# Pressure-Sensor-Module.net
KiCad netlist of a schematic drawn in EAGLE
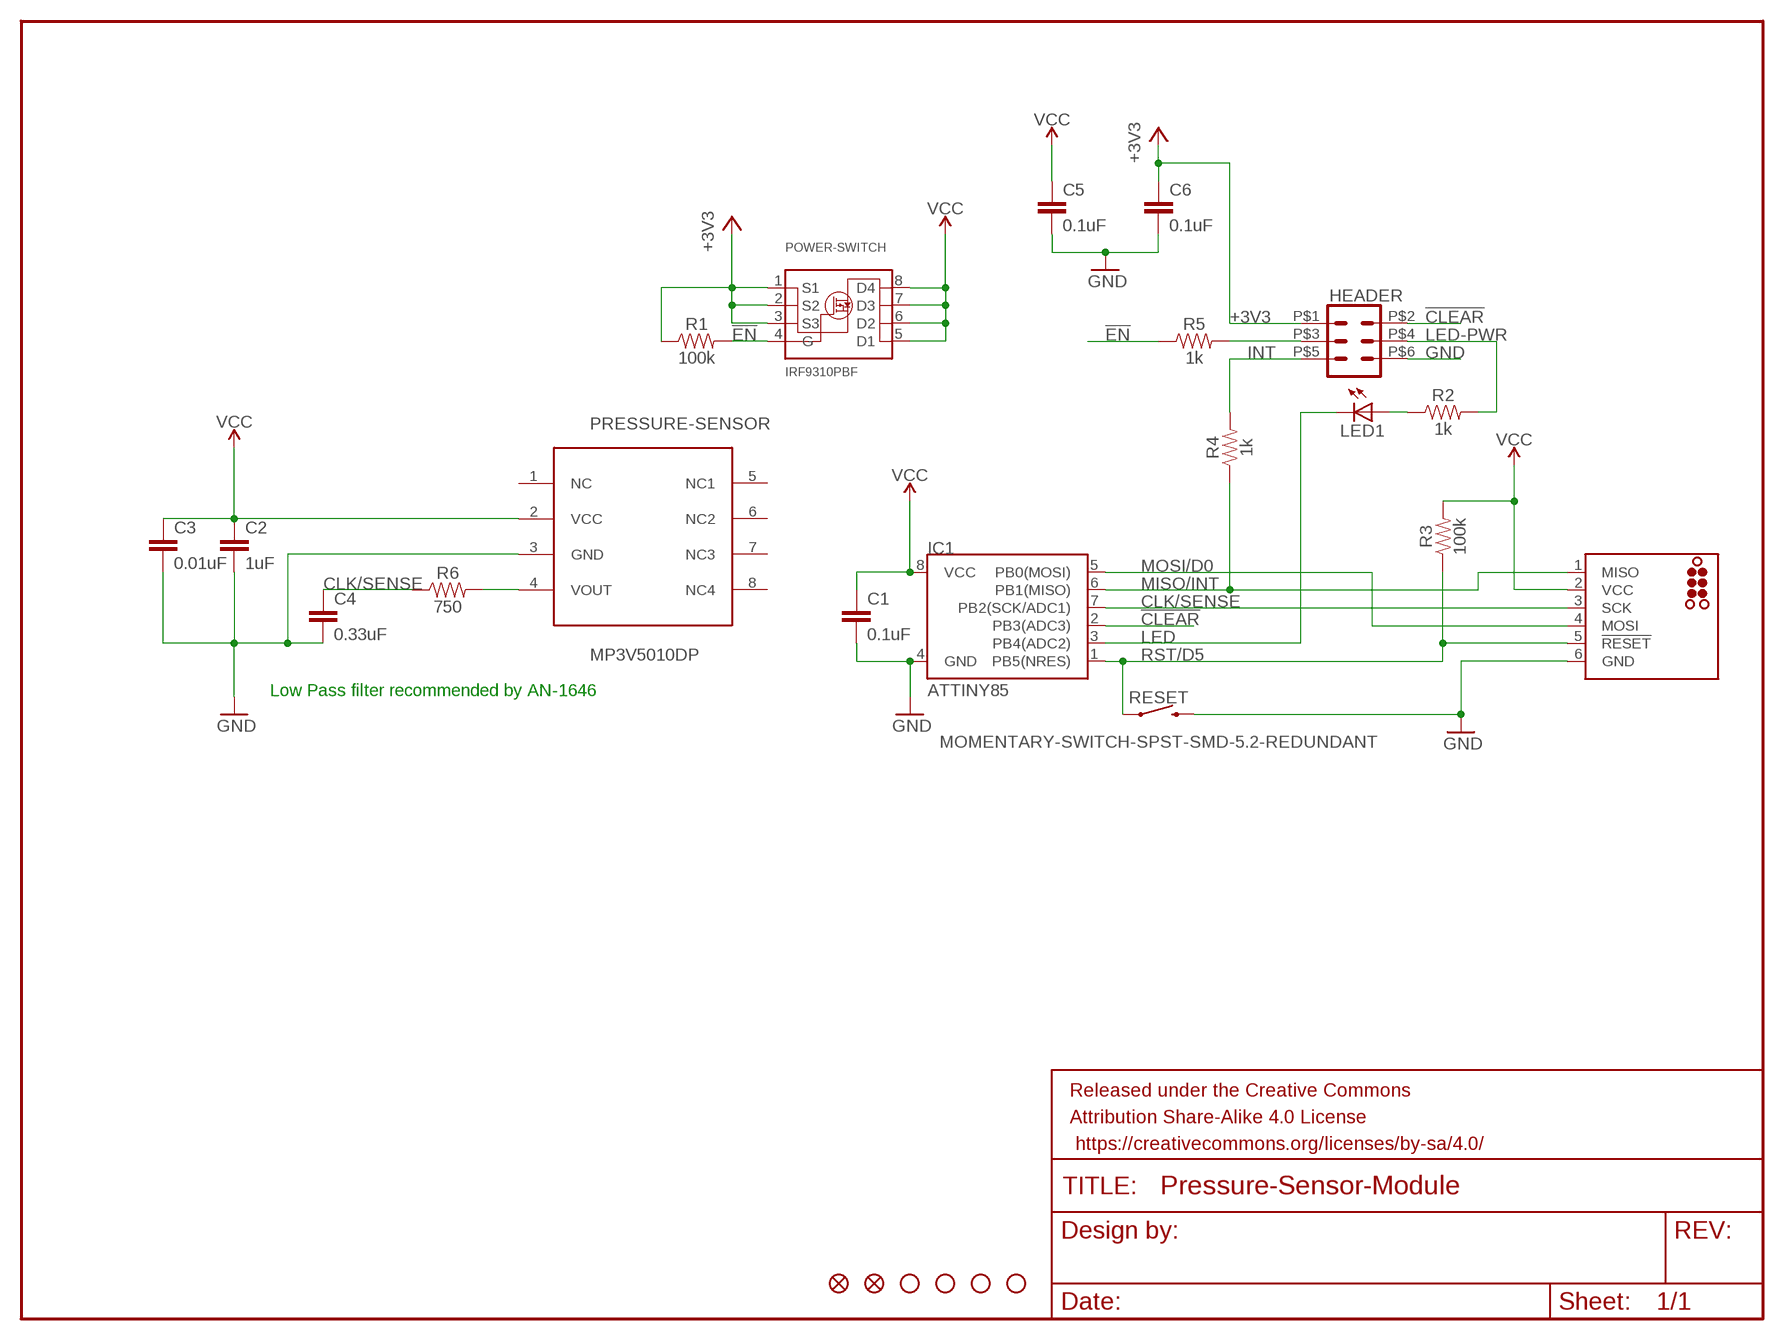
[diagram p0: schematic, sheet 1]

(export (version "E")
  (design (tool "Eeschema 10.0.6"))
  (components
    (comp (ref "C1")
      (value "0.1uF")
      (footprint "eagle-import:0805")
      (libsource (lib "eagle-import") (part "1.0UF-0805-25V-10%"))
    )
    (comp (ref "C2")
      (value "1uF")
      (footprint "eagle-import:0805")
      (libsource (lib "eagle-import") (part "1.0UF-0805-25V-10%"))
    )
    (comp (ref "C3")
      (value "0.01uF")
      (footprint "eagle-import:0805")
      (libsource (lib "eagle-import") (part "1.0UF-0805-25V-10%"))
    )
    (comp (ref "C4")
      (value "0.33uF")
      (footprint "eagle-import:0805")
      (libsource (lib "eagle-import") (part "1.0UF-0805-25V-10%"))
    )
    (comp (ref "C5")
      (value "0.1uF")
      (footprint "eagle-import:0805")
      (libsource (lib "eagle-import") (part "1.0UF-0805-25V-10%"))
    )
    (comp (ref "C6")
      (value "0.1uF")
      (footprint "eagle-import:0805")
      (libsource (lib "eagle-import") (part "1.0UF-0805-25V-10%"))
    )
    (comp (ref "FD1")
      (value "FIDUCIALUFIDUCIAL")
      (footprint "eagle-import:FIDUCIAL-MICRO")
      (libsource (lib "eagle-import") (part "FIDUCIALUFIDUCIAL"))
    )
    (comp (ref "FD2")
      (value "FIDUCIALUFIDUCIAL")
      (footprint "eagle-import:FIDUCIAL-MICRO")
      (libsource (lib "eagle-import") (part "FIDUCIALUFIDUCIAL"))
    )
    (comp (ref "FRAME1")
      (value "FRAME-LETTER")
      (footprint "eagle-import:CREATIVE_COMMONS")
      (libsource (lib "eagle-import") (part "FRAME-LETTER"))
    )
    (comp (ref "HEADER")
      (value "CONN_03X2POGO_PINS")
      (footprint "eagle-import:2X3_POGO")
      (libsource (lib "eagle-import") (part "CONN_03X2POGO_PINS"))
    )
    (comp (ref "IC1")
      (value "ATTINY85")
      (footprint "eagle-import:SO08-EIAJ")
      (libsource (lib "eagle-import") (part "ATTINY45"))
    )
    (comp (ref "ICSP")
      (value "TC2030-MCP-NL")
      (footprint "eagle-import:TC2030-MCP-NL")
      (libsource (lib "eagle-import") (part "TC2030-MCP-NL"))
    )
    (comp (ref "JP3")
      (value "STAND-OFF")
      (footprint "eagle-import:STAND-OFF")
      (libsource (lib "eagle-import") (part "STAND-OFF"))
    )
    (comp (ref "JP4")
      (value "STAND-OFF")
      (footprint "eagle-import:STAND-OFF")
      (libsource (lib "eagle-import") (part "STAND-OFF"))
    )
    (comp (ref "JP5")
      (value "STAND-OFF")
      (footprint "eagle-import:STAND-OFF")
      (libsource (lib "eagle-import") (part "STAND-OFF"))
    )
    (comp (ref "JP6")
      (value "STAND-OFF")
      (footprint "eagle-import:STAND-OFF")
      (libsource (lib "eagle-import") (part "STAND-OFF"))
    )
    (comp (ref "LED1")
      (value "LEDCHIP-LED0805")
      (footprint "eagle-import:CHIP-LED0805")
      (libsource (lib "eagle-import") (part "LEDCHIP-LED0805"))
    )
    (comp (ref "POWER-SWITCH")
      (value "IRF9310PBF")
      (footprint "eagle-import:SO8-GW300")
      (libsource (lib "eagle-import") (part "IRF9310PBF"))
    )
    (comp (ref "PRESSURE-SENSOR")
      (value "MP3V5010DP")
      (footprint "eagle-import:MP3V5010")
      (libsource (lib "eagle-import") (part "MP3V5010"))
    )
    (comp (ref "R1")
      (value "100k")
      (footprint "eagle-import:0805")
      (libsource (lib "eagle-import") (part "0.3OHM-0805-1/8W-1%"))
    )
    (comp (ref "R2")
      (value "1k")
      (footprint "eagle-import:0805")
      (libsource (lib "eagle-import") (part "0.3OHM-0805-1/8W-1%"))
    )
    (comp (ref "R3")
      (value "100k")
      (footprint "eagle-import:0805")
      (libsource (lib "eagle-import") (part "0.3OHM-0805-1/8W-1%"))
    )
    (comp (ref "R4")
      (value "1k")
      (footprint "eagle-import:0805")
      (libsource (lib "eagle-import") (part "0.3OHM-0805-1/8W-1%"))
    )
    (comp (ref "R5")
      (value "1k")
      (footprint "eagle-import:0805")
      (libsource (lib "eagle-import") (part "0.3OHM-0805-1/8W-1%"))
    )
    (comp (ref "R6")
      (value "750")
      (footprint "eagle-import:0805")
      (libsource (lib "eagle-import") (part "0.3OHM-0805-1/8W-1%"))
    )
    (comp (ref "RESET")
      (value "MOMENTARY-SWITCH-SPST-SMD-5.2-REDUNDANT")
      (footprint "eagle-import:TACTILE_SWITCH_SMD_5.2MM")
      (libsource (lib "eagle-import") (part "MOMENTARY-SWITCH-SPST-SMD-5.2-REDUNDANT"))
    )
  )
  (nets
    (net (code "1") (name "+3V3") (class "Default")
      (node (ref "C6") (pin "1") (pinfunction "1_1") (pintype "passive"))
      (node (ref "HEADER") (pin "P$1") (pinfunction "1_P$1") (pintype "bidirectional"))
      (node (ref "POWER-SWITCH") (pin "1") (pinfunction "S1_1") (pintype "bidirectional"))
      (node (ref "POWER-SWITCH") (pin "2") (pinfunction "S2_2") (pintype "bidirectional"))
      (node (ref "POWER-SWITCH") (pin "3") (pinfunction "S3_3") (pintype "bidirectional"))
      (node (ref "R1") (pin "1") (pinfunction "1_1") (pintype "passive"))
    )
    (net (code "2") (name "/CLK{slash}SENSE") (class "Default")
      (node (ref "C4") (pin "1") (pinfunction "1_1") (pintype "passive"))
      (node (ref "IC1") (pin "7") (pinfunction "PB2(SCK/ADC1)_7") (pintype "bidirectional"))
      (node (ref "ICSP") (pin "3") (pinfunction "SCK_3") (pintype "power_in"))
      (node (ref "R6") (pin "1") (pinfunction "1_1") (pintype "passive"))
    )
    (net (code "3") (name "/INT") (class "Default")
      (node (ref "HEADER") (pin "P$5") (pinfunction "5_P$5") (pintype "bidirectional"))
      (node (ref "R4") (pin "2") (pinfunction "2_2") (pintype "passive"))
    )
    (net (code "4") (name "/LED") (class "Default")
      (node (ref "IC1") (pin "3") (pinfunction "PB4(ADC2)_3") (pintype "bidirectional"))
      (node (ref "LED1") (pin "C") (pinfunction "C_C") (pintype "passive"))
    )
    (net (code "5") (name "/LED-PWR") (class "Default")
      (node (ref "HEADER") (pin "P$4") (pinfunction "4_P$4") (pintype "bidirectional"))
      (node (ref "R2") (pin "2") (pinfunction "2_2") (pintype "passive"))
    )
    (net (code "6") (name "/MISO{slash}INT") (class "Default")
      (node (ref "IC1") (pin "6") (pinfunction "PB1(MISO)_6") (pintype "bidirectional"))
      (node (ref "ICSP") (pin "1") (pinfunction "MISO_1") (pintype "passive"))
      (node (ref "R4") (pin "1") (pinfunction "1_1") (pintype "passive"))
    )
    (net (code "7") (name "/MOSI{slash}D0") (class "Default")
      (node (ref "IC1") (pin "5") (pinfunction "PB0(MOSI)_5") (pintype "bidirectional"))
      (node (ref "ICSP") (pin "4") (pinfunction "MOSI_4") (pintype "bidirectional"))
    )
    (net (code "8") (name "/NC") (class "Default")
      (node (ref "PRESSURE-SENSOR") (pin "1") (pinfunction "NC_1") (pintype "power_in"))
    )
    (net (code "9") (name "/NC1") (class "Default")
      (node (ref "PRESSURE-SENSOR") (pin "5") (pinfunction "NC1_5") (pintype "power_in"))
    )
    (net (code "10") (name "/RST{slash}D5") (class "Default")
      (node (ref "IC1") (pin "1") (pinfunction "PB5(NRES)_1") (pintype "bidirectional"))
      (node (ref "ICSP") (pin "5") (pinfunction "~{RESET}_5") (pintype "output"))
      (node (ref "R3") (pin "1") (pinfunction "1_1") (pintype "passive"))
      (node (ref "RESET") (pin "1") (pinfunction "1_1") (pintype "passive"))
      (node (ref "RESET") (pin "2") (pinfunction "1_2") (pintype "passive"))
    )
    (net (code "11") (name "/~{CLEAR}") (class "Default")
      (node (ref "HEADER") (pin "P$2") (pinfunction "2_P$2") (pintype "bidirectional"))
      (node (ref "IC1") (pin "2") (pinfunction "PB3(ADC3)_2") (pintype "bidirectional"))
    )
    (net (code "12") (name "/~{EN}") (class "Default")
      (node (ref "POWER-SWITCH") (pin "4") (pinfunction "G_4") (pintype "bidirectional"))
      (node (ref "R1") (pin "2") (pinfunction "2_2") (pintype "passive"))
      (node (ref "R5") (pin "1") (pinfunction "1_1") (pintype "passive"))
    )
    (net (code "13") (name "GND") (class "Default")
      (node (ref "C1") (pin "2") (pinfunction "2_2") (pintype "passive"))
      (node (ref "C2") (pin "2") (pinfunction "2_2") (pintype "passive"))
      (node (ref "C3") (pin "2") (pinfunction "2_2") (pintype "passive"))
      (node (ref "C4") (pin "2") (pinfunction "2_2") (pintype "passive"))
      (node (ref "C5") (pin "2") (pinfunction "2_2") (pintype "passive"))
      (node (ref "C6") (pin "2") (pinfunction "2_2") (pintype "passive"))
      (node (ref "HEADER") (pin "P$6") (pinfunction "6_P$6") (pintype "bidirectional"))
      (node (ref "IC1") (pin "4") (pinfunction "GND_4") (pintype "bidirectional"))
      (node (ref "ICSP") (pin "6") (pinfunction "GND_6") (pintype "bidirectional"))
      (node (ref "PRESSURE-SENSOR") (pin "3") (pinfunction "GND_3") (pintype "bidirectional"))
      (node (ref "RESET") (pin "3") (pinfunction "2_3") (pintype "passive"))
      (node (ref "RESET") (pin "4") (pinfunction "2_4") (pintype "passive"))
    )
    (net (code "14") (name "Net-(HEADER-3)") (class "Default")
      (node (ref "HEADER") (pin "P$3") (pinfunction "3_P$3") (pintype "bidirectional"))
      (node (ref "R5") (pin "2") (pinfunction "2_2") (pintype "passive"))
    )
    (net (code "15") (name "Net-(LED1-PadA)") (class "Default")
      (node (ref "LED1") (pin "A") (pinfunction "A_A") (pintype "passive"))
      (node (ref "R2") (pin "1") (pinfunction "1_1") (pintype "passive"))
    )
    (net (code "16") (name "Net-(PRESSURE-SENSOR-VOUT)") (class "Default")
      (node (ref "PRESSURE-SENSOR") (pin "4") (pinfunction "VOUT_4") (pintype "bidirectional"))
      (node (ref "R6") (pin "2") (pinfunction "2_2") (pintype "passive"))
    )
    (net (code "17") (name "VCC") (class "Default")
      (node (ref "C1") (pin "1") (pinfunction "1_1") (pintype "passive"))
      (node (ref "C2") (pin "1") (pinfunction "1_1") (pintype "passive"))
      (node (ref "C3") (pin "1") (pinfunction "1_1") (pintype "passive"))
      (node (ref "C5") (pin "1") (pinfunction "1_1") (pintype "passive"))
      (node (ref "IC1") (pin "8") (pinfunction "VCC_8") (pintype "bidirectional"))
      (node (ref "ICSP") (pin "2") (pinfunction "VCC_2") (pintype "power_in"))
      (node (ref "POWER-SWITCH") (pin "5") (pinfunction "D1_5") (pintype "bidirectional"))
      (node (ref "POWER-SWITCH") (pin "6") (pinfunction "D2_6") (pintype "bidirectional"))
      (node (ref "POWER-SWITCH") (pin "7") (pinfunction "D3_7") (pintype "bidirectional"))
      (node (ref "POWER-SWITCH") (pin "8") (pinfunction "D4_8") (pintype "bidirectional"))
      (node (ref "PRESSURE-SENSOR") (pin "2") (pinfunction "VCC_2") (pintype "bidirectional"))
      (node (ref "R3") (pin "2") (pinfunction "2_2") (pintype "passive"))
    )
    (net (code "18") (name "unconnected-(PRESSURE-SENSOR-NC2-Pad6)") (class "Default")
      (node (ref "PRESSURE-SENSOR") (pin "6") (pinfunction "NC2_6") (pintype "bidirectional"))
    )
    (net (code "19") (name "unconnected-(PRESSURE-SENSOR-NC3-Pad7)") (class "Default")
      (node (ref "PRESSURE-SENSOR") (pin "7") (pinfunction "NC3_7") (pintype "bidirectional"))
    )
    (net (code "20") (name "unconnected-(PRESSURE-SENSOR-NC4-Pad8)") (class "Default")
      (node (ref "PRESSURE-SENSOR") (pin "8") (pinfunction "NC4_8") (pintype "output"))
    )
  )
)
